# kd_inz_BL653.net
KiCad netlist of a schematic drawn in Altium Designer
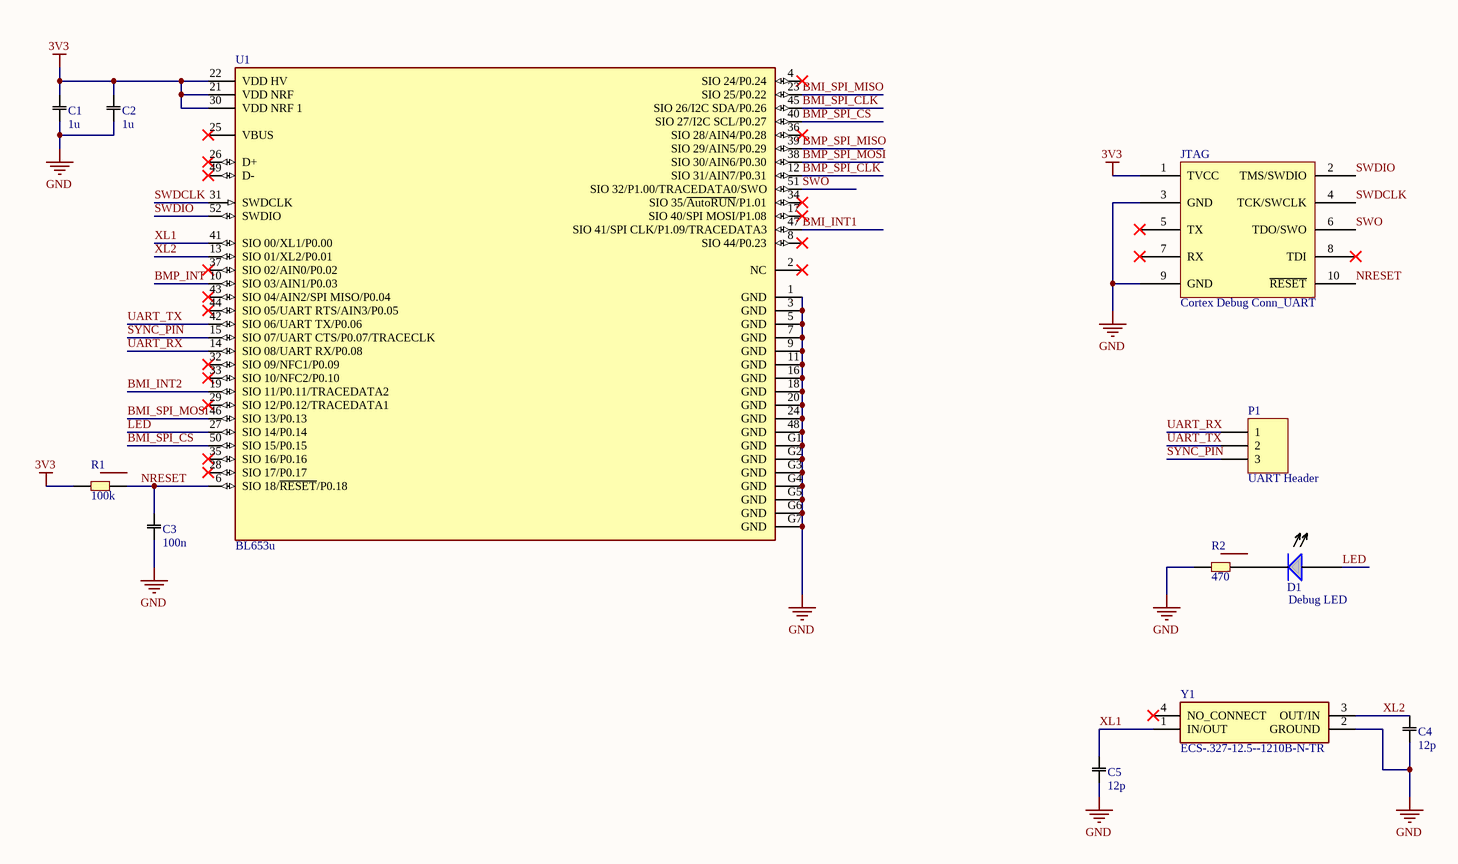
[diagram p0: kd_inz_BL653.SchDoc]

(export (version "E")
  (design (tool "Eeschema 10.0.6"))
  (components
    (comp (ref "C1")
      (value "1u")
      (footprint "0402")
      (description "Capacitor")
      (libsource (lib "basic_lib_v1-2") (part "C"))
    )
    (comp (ref "C2")
      (value "1u")
      (footprint "0402")
      (description "Capacitor")
      (libsource (lib "basic_lib_v1-2") (part "C"))
    )
    (comp (ref "C3")
      (value "100n")
      (footprint "0402")
      (description "Capacitor")
      (libsource (lib "basic_lib_v1-2") (part "C"))
    )
    (comp (ref "C4")
      (value "12p")
      (footprint "0402")
      (description "Capacitor")
      (libsource (lib "basic_lib_v1-2") (part "C"))
    )
    (comp (ref "C5")
      (value "12p")
      (footprint "0402")
      (description "Capacitor")
      (libsource (lib "basic_lib_v1-2") (part "C"))
    )
    (comp (ref "D1") (value "Debug LED") (footprint "0402") (libsource (lib "basic_lib_v1-2") (part "LED")))
    (comp (ref "JTAG")
      (value "Cortex Debug Conn_UART")
      (footprint "Cortex Debug Connector - THT")
      (libsource (lib "basic_lib_v1-2") (part "Cortex Debug Conn_UART"))
    )
    (comp (ref "P1")
      (value "UART Header")
      (footprint "HDR1X3")
      (description "Header, 3-Pin")
      (fields (field (name "PUBLISHER") "Altium Limited"))
      (libsource (lib "Miscellaneous Connectors") (part "Header 3"))
    )
    (comp (ref "R1")
      (value "100k")
      (footprint "0402")
      (description "Resistor")
      (libsource (lib "basic_lib_v1-2") (part "R"))
    )
    (comp (ref "R2")
      (value "470")
      (footprint "0402")
      (description "Resistor")
      (libsource (lib "basic_lib_v1-2") (part "R"))
    )
    (comp (ref "U1")
      (value "BL653u")
      (footprint "kd_lib:FP-453-00059R-MFG")
      (description "BL653 MOD INTEGRATED ANT")
      (libsource (lib "kd_lib") (part "BL653u"))
    )
    (comp (ref "Y1")
      (value "ECS-.327-12.5--1210B-N-TR")
      (footprint "kd_lib:ECS3271251210BNTR")
      (description "Crystal or Oscillator")
      (libsource (lib "kd_lib") (part "ECS-.327-12.5--1210B-N-TR"))
    )
  )
  (nets
    (net (code "1") (name "/BMI_INT1") (class "Default")
      (node (ref "U1") (pin "47") (pinfunction "SIO_41/SPI_CLK/P1.09/TRACEDATA3_47") (pintype "bidirectional"))
    )
    (net (code "2") (name "/BMI_INT2") (class "Default")
      (node (ref "U1") (pin "19") (pinfunction "SIO_11/P0.11/TRACEDATA2_19") (pintype "bidirectional"))
    )
    (net (code "3") (name "/BMI_SPI_CLK") (class "Default")
      (node (ref "U1") (pin "45") (pinfunction "SIO_26/I2C_SDA/P0.26_45") (pintype "bidirectional"))
    )
    (net (code "4") (name "/BMI_SPI_CS") (class "Default")
      (node (ref "U1") (pin "50") (pinfunction "SIO_15/P0.15_50") (pintype "bidirectional"))
    )
    (net (code "5") (name "/BMI_SPI_MISO") (class "Default")
      (node (ref "U1") (pin "23") (pinfunction "SIO_25/P0.22_23") (pintype "bidirectional"))
    )
    (net (code "6") (name "/BMI_SPI_MOSI") (class "Default")
      (node (ref "U1") (pin "46") (pinfunction "SIO_13/P0.13_46") (pintype "bidirectional"))
    )
    (net (code "7") (name "/BMP_INT") (class "Default")
      (node (ref "U1") (pin "10") (pinfunction "SIO_03/AIN1/P0.03_10") (pintype "bidirectional"))
    )
    (net (code "8") (name "/BMP_SPI_CLK") (class "Default")
      (node (ref "U1") (pin "12") (pinfunction "SIO_31/AIN7/P0.31_12") (pintype "bidirectional"))
    )
    (net (code "9") (name "/BMP_SPI_CS") (class "Default")
      (node (ref "U1") (pin "40") (pinfunction "SIO_27/I2C_SCL/P0.27_40") (pintype "bidirectional"))
    )
    (net (code "10") (name "/BMP_SPI_MISO") (class "Default")
      (node (ref "U1") (pin "39") (pinfunction "SIO_29/AIN5/P0.29_39") (pintype "bidirectional"))
    )
    (net (code "11") (name "/BMP_SPI_MOSI") (class "Default")
      (node (ref "U1") (pin "38") (pinfunction "SIO_30/AIN6/P0.30_38") (pintype "bidirectional"))
    )
    (net (code "12") (name "/LED") (class "Default")
      (node (ref "D1") (pin "2") (pinfunction "2_2") (pintype "passive"))
      (node (ref "U1") (pin "27") (pinfunction "SIO_14/P0.14_27") (pintype "bidirectional"))
    )
    (net (code "13") (name "/NRESET") (class "Default")
      (node (ref "C3") (pin "2") (pintype "passive"))
      (node (ref "JTAG") (pin "10") (pinfunction "~{RESET}_10") (pintype "passive"))
      (node (ref "R1") (pin "2") (pintype "passive"))
      (node (ref "U1") (pin "6") (pinfunction "SIO_18/~{RESET}/P0.18_6") (pintype "bidirectional"))
    )
    (net (code "14") (name "/SWDCLK") (class "Default")
      (node (ref "JTAG") (pin "4") (pinfunction "TCK/SWCLK_4") (pintype "passive"))
      (node (ref "U1") (pin "31") (pinfunction "SWDCLK_31") (pintype "input"))
    )
    (net (code "15") (name "/SWDIO") (class "Default")
      (node (ref "JTAG") (pin "2") (pinfunction "TMS/SWDIO_2") (pintype "passive"))
      (node (ref "U1") (pin "52") (pinfunction "SWDIO_52") (pintype "bidirectional"))
    )
    (net (code "16") (name "/SWO") (class "Default")
      (node (ref "JTAG") (pin "6") (pinfunction "TDO/SWO_6") (pintype "passive"))
      (node (ref "U1") (pin "51") (pinfunction "SIO_32/P1.00/TRACEDATA0/SWO_51") (pintype "bidirectional"))
    )
    (net (code "17") (name "/SYNC_PIN") (class "Default")
      (node (ref "P1") (pin "3") (pinfunction "3_3") (pintype "passive"))
      (node (ref "U1") (pin "15") (pinfunction "SIO_07/UART_CTS/P0.07/TRACECLK_15") (pintype "bidirectional"))
    )
    (net (code "18") (name "/UART_RX") (class "Default")
      (node (ref "P1") (pin "1") (pinfunction "1_1") (pintype "passive"))
      (node (ref "U1") (pin "14") (pinfunction "SIO_08/UART_RX/P0.08_14") (pintype "bidirectional"))
    )
    (net (code "19") (name "/UART_TX") (class "Default")
      (node (ref "P1") (pin "2") (pinfunction "2_2") (pintype "passive"))
      (node (ref "U1") (pin "42") (pinfunction "SIO_06/UART_TX/P0.06_42") (pintype "bidirectional"))
    )
    (net (code "20") (name "/XL1") (class "Default")
      (node (ref "C5") (pin "2") (pintype "passive"))
      (node (ref "U1") (pin "41") (pinfunction "SIO_00/XL1/P0.00_41") (pintype "bidirectional"))
      (node (ref "Y1") (pin "1") (pinfunction "IN/OUT_1") (pintype "passive"))
    )
    (net (code "21") (name "/XL2") (class "Default")
      (node (ref "C4") (pin "2") (pintype "passive"))
      (node (ref "U1") (pin "13") (pinfunction "SIO_01/XL2/P0.01_13") (pintype "bidirectional"))
      (node (ref "Y1") (pin "3") (pinfunction "OUT/IN_3") (pintype "passive"))
    )
    (net (code "22") (name "3V3") (class "Default")
      (node (ref "C1") (pin "2") (pintype "passive"))
      (node (ref "C2") (pin "2") (pintype "passive"))
      (node (ref "JTAG") (pin "1") (pinfunction "TVCC_1") (pintype "passive"))
      (node (ref "R1") (pin "1") (pintype "passive"))
      (node (ref "U1") (pin "21") (pinfunction "VDD_NRF_21") (pintype "power_in"))
      (node (ref "U1") (pin "22") (pinfunction "VDD_HV_22") (pintype "power_in"))
      (node (ref "U1") (pin "30") (pinfunction "VDD_NRF_1_30") (pintype "power_in"))
    )
    (net (code "23") (name "GND") (class "Default")
      (node (ref "C1") (pin "1") (pintype "passive"))
      (node (ref "C2") (pin "1") (pintype "passive"))
      (node (ref "C3") (pin "1") (pintype "passive"))
      (node (ref "C4") (pin "1") (pintype "passive"))
      (node (ref "C5") (pin "1") (pintype "passive"))
      (node (ref "JTAG") (pin "3") (pinfunction "GND_3") (pintype "passive"))
      (node (ref "JTAG") (pin "9") (pinfunction "GND_9") (pintype "passive"))
      (node (ref "R2") (pin "1") (pintype "passive"))
      (node (ref "U1") (pin "1") (pinfunction "GND_1") (pintype "power_in"))
      (node (ref "U1") (pin "11") (pinfunction "GND_11") (pintype "power_in"))
      (node (ref "U1") (pin "16") (pinfunction "GND_16") (pintype "power_in"))
      (node (ref "U1") (pin "18") (pinfunction "GND_18") (pintype "power_in"))
      (node (ref "U1") (pin "20") (pinfunction "GND_20") (pintype "power_in"))
      (node (ref "U1") (pin "24") (pinfunction "GND_24") (pintype "power_in"))
      (node (ref "U1") (pin "3") (pinfunction "GND_3") (pintype "power_in"))
      (node (ref "U1") (pin "48") (pinfunction "GND_48") (pintype "power_in"))
      (node (ref "U1") (pin "5") (pinfunction "GND_5") (pintype "power_in"))
      (node (ref "U1") (pin "7") (pinfunction "GND_7") (pintype "power_in"))
      (node (ref "U1") (pin "9") (pinfunction "GND_9") (pintype "power_in"))
      (node (ref "U1") (pin "G1") (pinfunction "GND_G1") (pintype "power_in"))
      (node (ref "U1") (pin "G2") (pinfunction "GND_G2") (pintype "power_in"))
      (node (ref "U1") (pin "G3") (pinfunction "GND_G3") (pintype "power_in"))
      (node (ref "U1") (pin "G4") (pinfunction "GND_G4") (pintype "power_in"))
      (node (ref "U1") (pin "G5") (pinfunction "GND_G5") (pintype "power_in"))
      (node (ref "U1") (pin "G6") (pinfunction "GND_G6") (pintype "power_in"))
      (node (ref "U1") (pin "G7") (pinfunction "GND_G7") (pintype "power_in"))
      (node (ref "Y1") (pin "2") (pinfunction "GROUND_2") (pintype "passive"))
    )
    (net (code "24") (name "Net-(D1-Pad1)") (class "Default")
      (node (ref "D1") (pin "1") (pinfunction "1_1") (pintype "passive"))
      (node (ref "R2") (pin "2") (pintype "passive"))
    )
    (net (code "25") (name "unconnected-(JTAG-RX-Pad7)") (class "Default")
      (node (ref "JTAG") (pin "7") (pinfunction "RX_7") (pintype "passive+no_connect"))
    )
    (net (code "26") (name "unconnected-(JTAG-TDI-Pad8)") (class "Default")
      (node (ref "JTAG") (pin "8") (pinfunction "TDI_8") (pintype "passive+no_connect"))
    )
    (net (code "27") (name "unconnected-(JTAG-TX-Pad5)") (class "Default")
      (node (ref "JTAG") (pin "5") (pinfunction "TX_5") (pintype "passive+no_connect"))
    )
    (net (code "28") (name "unconnected-(U1-D+-Pad26)") (class "Default")
      (node (ref "U1") (pin "26") (pinfunction "D+_26") (pintype "bidirectional+no_connect"))
    )
    (net (code "29") (name "unconnected-(U1-D--Pad49)") (class "Default")
      (node (ref "U1") (pin "49") (pinfunction "D-_49") (pintype "bidirectional+no_connect"))
    )
    (net (code "30") (name "unconnected-(U1-NC-Pad2)") (class "Default")
      (node (ref "U1") (pin "2") (pinfunction "NC_2") (pintype "passive+no_connect"))
    )
    (net (code "31") (name "unconnected-(U1-SIO_02{slash}AIN0{slash}P0.02-Pad37)") (class "Default")
      (node (ref "U1") (pin "37") (pinfunction "SIO_02/AIN0/P0.02_37") (pintype "bidirectional+no_connect"))
    )
    (net (code "32") (name "unconnected-(U1-SIO_04{slash}AIN2{slash}SPI_MISO{slash}P0.04-Pad43)") (class "Default")
      (node (ref "U1") (pin "43") (pinfunction "SIO_04/AIN2/SPI_MISO/P0.04_43") (pintype "bidirectional+no_connect"))
    )
    (net (code "33") (name "unconnected-(U1-SIO_05{slash}UART_RTS{slash}AIN3{slash}P0.05-Pad44)") (class "Default")
      (node (ref "U1") (pin "44") (pinfunction "SIO_05/UART_RTS/AIN3/P0.05_44") (pintype "bidirectional+no_connect"))
    )
    (net (code "34") (name "unconnected-(U1-SIO_09{slash}NFC1{slash}P0.09-Pad32)") (class "Default")
      (node (ref "U1") (pin "32") (pinfunction "SIO_09/NFC1/P0.09_32") (pintype "bidirectional+no_connect"))
    )
    (net (code "35") (name "unconnected-(U1-SIO_10{slash}NFC2{slash}P0.10-Pad33)") (class "Default")
      (node (ref "U1") (pin "33") (pinfunction "SIO_10/NFC2/P0.10_33") (pintype "bidirectional+no_connect"))
    )
    (net (code "36") (name "unconnected-(U1-SIO_12{slash}P0.12{slash}TRACEDATA1-Pad29)") (class "Default")
      (node (ref "U1") (pin "29") (pinfunction "SIO_12/P0.12/TRACEDATA1_29") (pintype "bidirectional+no_connect"))
    )
    (net (code "37") (name "unconnected-(U1-SIO_16{slash}P0.16-Pad35)") (class "Default")
      (node (ref "U1") (pin "35") (pinfunction "SIO_16/P0.16_35") (pintype "bidirectional+no_connect"))
    )
    (net (code "38") (name "unconnected-(U1-SIO_17{slash}P0.17-Pad28)") (class "Default")
      (node (ref "U1") (pin "28") (pinfunction "SIO_17/P0.17_28") (pintype "bidirectional+no_connect"))
    )
    (net (code "39") (name "unconnected-(U1-SIO_24{slash}P0.24-Pad4)") (class "Default")
      (node (ref "U1") (pin "4") (pinfunction "SIO_24/P0.24_4") (pintype "bidirectional+no_connect"))
    )
    (net (code "40") (name "unconnected-(U1-SIO_28{slash}AIN4{slash}P0.28-Pad36)") (class "Default")
      (node (ref "U1") (pin "36") (pinfunction "SIO_28/AIN4/P0.28_36") (pintype "bidirectional+no_connect"))
    )
    (net (code "41") (name "unconnected-(U1-SIO_35{slash}~{AutoRUN}{slash}P1.01-Pad34)") (class "Default")
      (node (ref "U1") (pin "34") (pinfunction "SIO_35/~{AutoRUN}/P1.01_34") (pintype "bidirectional+no_connect"))
    )
    (net (code "42") (name "unconnected-(U1-SIO_40{slash}SPI_MOSI{slash}P1.08-Pad17)") (class "Default")
      (node (ref "U1") (pin "17") (pinfunction "SIO_40/SPI_MOSI/P1.08_17") (pintype "bidirectional+no_connect"))
    )
    (net (code "43") (name "unconnected-(U1-SIO_44{slash}P0.23-Pad8)") (class "Default")
      (node (ref "U1") (pin "8") (pinfunction "SIO_44/P0.23_8") (pintype "bidirectional+no_connect"))
    )
    (net (code "44") (name "unconnected-(U1-VBUS-Pad25)") (class "Default")
      (node (ref "U1") (pin "25") (pinfunction "VBUS_25") (pintype "power_in+no_connect"))
    )
    (net (code "45") (name "unconnected-(Y1-NO_CONNECT-Pad4)") (class "Default")
      (node (ref "Y1") (pin "4") (pinfunction "NO_CONNECT_4") (pintype "passive+no_connect"))
    )
  )
)
